# Sheet1.net
KiCad netlist of a schematic drawn in Altium Designer
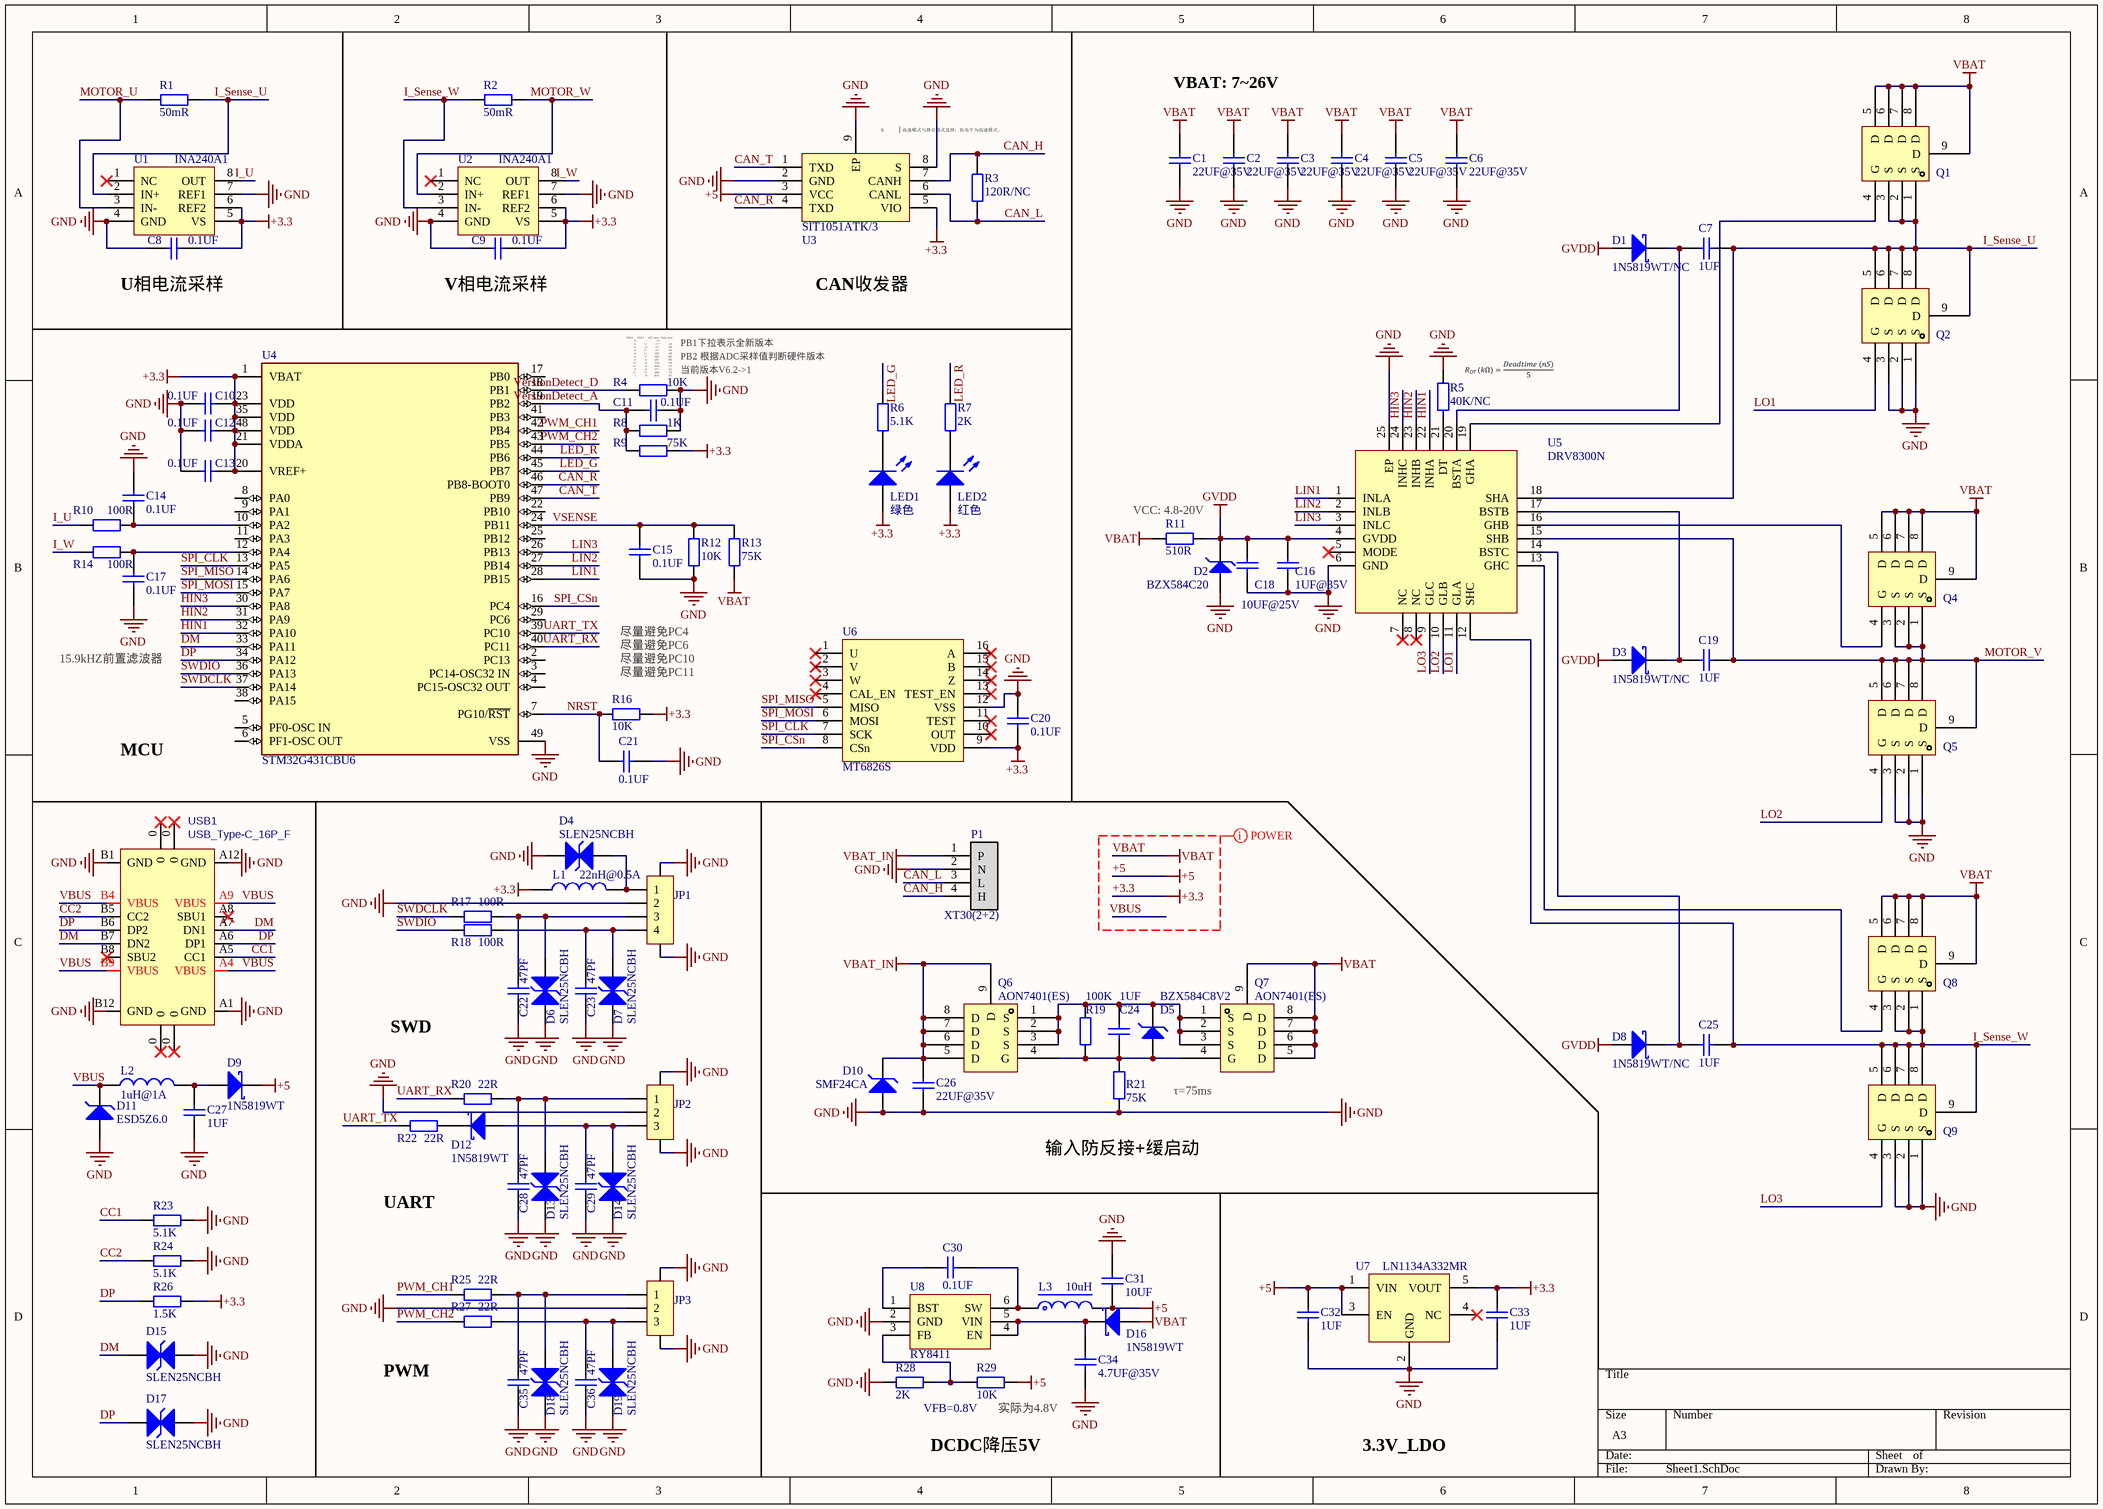
[diagram p0: Sheet1.SchDoc]

(export (version "E")
  (design (tool "Eeschema 10.0.6"))
  (components
    (comp (ref "C1")
      (value "22UF@35V")
      (footprint "C1206_NS")
      (description "贴片电容/MLCC电容")
      (libsource (lib "阻容") (part "C"))
    )
    (comp (ref "C2")
      (value "22UF@35V")
      (footprint "C1206_NS")
      (description "贴片电容/MLCC电容")
      (libsource (lib "阻容") (part "C"))
    )
    (comp (ref "C3")
      (value "22UF@35V")
      (footprint "C1206_NS")
      (description "贴片电容/MLCC电容")
      (libsource (lib "阻容") (part "C"))
    )
    (comp (ref "C4")
      (value "22UF@35V")
      (footprint "C1206_NS")
      (description "贴片电容/MLCC电容")
      (libsource (lib "阻容") (part "C"))
    )
    (comp (ref "C5")
      (value "22UF@35V")
      (footprint "C1206_NS")
      (description "贴片电容/MLCC电容")
      (libsource (lib "阻容") (part "C"))
    )
    (comp (ref "C6")
      (value "22UF@35V")
      (footprint "C1206_NS")
      (description "贴片电容/MLCC电容")
      (libsource (lib "阻容") (part "C"))
    )
    (comp (ref "C7")
      (value "1UF")
      (footprint "C0603_NS")
      (description "贴片电容/MLCC电容")
      (libsource (lib "阻容") (part "C"))
    )
    (comp (ref "C8")
      (value "0.1UF")
      (footprint "C0402_NS")
      (description "贴片电容/MLCC电容")
      (libsource (lib "阻容") (part "C"))
    )
    (comp (ref "C9")
      (value "0.1UF")
      (footprint "C0402_NS")
      (description "贴片电容/MLCC电容")
      (libsource (lib "阻容") (part "C"))
    )
    (comp (ref "C10")
      (value "0.1UF")
      (footprint "C0402_NS")
      (description "贴片电容/MLCC电容")
      (libsource (lib "阻容") (part "C"))
    )
    (comp (ref "C11")
      (value "0.1UF")
      (footprint "C0402_NS")
      (description "贴片电容/MLCC电容")
      (libsource (lib "阻容") (part "C"))
    )
    (comp (ref "C12")
      (value "0.1UF")
      (footprint "C0402_NS")
      (description "贴片电容/MLCC电容")
      (libsource (lib "阻容") (part "C"))
    )
    (comp (ref "C13")
      (value "0.1UF")
      (footprint "C0402_NS")
      (description "贴片电容/MLCC电容")
      (libsource (lib "阻容") (part "C"))
    )
    (comp (ref "C14")
      (value "0.1UF")
      (footprint "C0402_NS")
      (description "贴片电容/MLCC电容")
      (libsource (lib "阻容") (part "C"))
    )
    (comp (ref "C15")
      (value "0.1UF")
      (footprint "C0402_NS")
      (description "贴片电容/MLCC电容")
      (libsource (lib "阻容") (part "C"))
    )
    (comp (ref "C16")
      (value "1UF@35V")
      (footprint "C0603_NS")
      (description "贴片电容/MLCC电容")
      (libsource (lib "阻容") (part "C"))
    )
    (comp (ref "C17")
      (value "0.1UF")
      (footprint "C0402_NS")
      (description "贴片电容/MLCC电容")
      (libsource (lib "阻容") (part "C"))
    )
    (comp (ref "C18")
      (value "10UF@25V")
      (footprint "C0603_NS")
      (description "贴片电容/MLCC电容")
      (libsource (lib "阻容") (part "C"))
    )
    (comp (ref "C19")
      (value "1UF")
      (footprint "C0603_NS")
      (description "贴片电容/MLCC电容")
      (libsource (lib "阻容") (part "C"))
    )
    (comp (ref "C20")
      (value "0.1UF")
      (footprint "C0402_NS")
      (description "贴片电容/MLCC电容")
      (libsource (lib "阻容") (part "C"))
    )
    (comp (ref "C21")
      (value "0.1UF")
      (footprint "C0402_NS")
      (description "贴片电容/MLCC电容")
      (libsource (lib "阻容") (part "C"))
    )
    (comp (ref "C22")
      (value "47PF")
      (footprint "C0402_NS")
      (description "贴片电容/MLCC电容")
      (libsource (lib "阻容") (part "C"))
    )
    (comp (ref "C23")
      (value "47PF")
      (footprint "C0402_NS")
      (description "贴片电容/MLCC电容")
      (libsource (lib "阻容") (part "C"))
    )
    (comp (ref "C24")
      (value "1UF")
      (footprint "C0402_NS")
      (description "贴片电容/MLCC电容")
      (libsource (lib "阻容") (part "C"))
    )
    (comp (ref "C25")
      (value "1UF")
      (footprint "C0603_NS")
      (description "贴片电容/MLCC电容")
      (libsource (lib "阻容") (part "C"))
    )
    (comp (ref "C26")
      (value "22UF@35V")
      (footprint "C1206_NS")
      (description "贴片电容/MLCC电容")
      (libsource (lib "阻容") (part "C"))
    )
    (comp (ref "C27")
      (value "1UF")
      (footprint "C0603_NS")
      (description "贴片电容/MLCC电容")
      (libsource (lib "阻容") (part "C"))
    )
    (comp (ref "C28")
      (value "47PF")
      (footprint "C0402_NS")
      (description "贴片电容/MLCC电容")
      (libsource (lib "阻容") (part "C"))
    )
    (comp (ref "C29")
      (value "47PF")
      (footprint "C0402_NS")
      (description "贴片电容/MLCC电容")
      (libsource (lib "阻容") (part "C"))
    )
    (comp (ref "C30")
      (value "0.1UF")
      (footprint "C0402_NS")
      (description "贴片电容/MLCC电容")
      (libsource (lib "阻容") (part "C"))
    )
    (comp (ref "C31")
      (value "10UF")
      (footprint "C0805_NS")
      (description "贴片电容/MLCC电容")
      (libsource (lib "阻容") (part "C"))
    )
    (comp (ref "C32")
      (value "1UF")
      (footprint "C0402_NS")
      (description "贴片电容/MLCC电容")
      (libsource (lib "阻容") (part "C"))
    )
    (comp (ref "C33")
      (value "1UF")
      (footprint "C0402_NS")
      (description "贴片电容/MLCC电容")
      (libsource (lib "阻容") (part "C"))
    )
    (comp (ref "C34")
      (value "4.7UF@35V")
      (footprint "C0805_NS")
      (description "贴片电容/MLCC电容")
      (libsource (lib "阻容") (part "C"))
    )
    (comp (ref "C35")
      (value "47PF")
      (footprint "C0402_NS")
      (description "贴片电容/MLCC电容")
      (libsource (lib "阻容") (part "C"))
    )
    (comp (ref "C36")
      (value "47PF")
      (footprint "C0402_NS")
      (description "贴片电容/MLCC电容")
      (libsource (lib "阻容") (part "C"))
    )
    (comp (ref "D1")
      (value "1N5819WT/NC")
      (footprint "SOD-523")
      (description "肖特基二极管")
      (libsource (lib "二极管(含LED)") (part "SSXX"))
    )
    (comp (ref "D2")
      (value "BZX584C20")
      (footprint "SOD-523")
      (description "稳压二极管")
      (fields (field (name "VOLTAGE") "5.1V"))
      (libsource (lib "二极管(含LED)") (part "MM1ZXX"))
    )
    (comp (ref "D3")
      (value "1N5819WT/NC")
      (footprint "SOD-523")
      (description "肖特基二极管")
      (libsource (lib "二极管(含LED)") (part "SSXX"))
    )
    (comp (ref "D4")
      (value "SLEN25NCBH")
      (footprint "DFN1006-2L_L1.0_W0.6_P0.7")
      (description "双向静电和浪涌保护(TVS/ESD)")
      (libsource (lib "二极管(含LED)") (part "PESD5V0F1BL"))
    )
    (comp (ref "D5")
      (value "BZX584C8V2")
      (footprint "SOD-523")
      (description "稳压二极管")
      (fields (field (name "VOLTAGE") "5.1V"))
      (libsource (lib "二极管(含LED)") (part "MM1ZXX"))
    )
    (comp (ref "D6")
      (value "SLEN25NCBH")
      (footprint "DFN1006-2L_L1.0_W0.6_P0.7")
      (description "双向静电和浪涌保护(TVS/ESD)")
      (libsource (lib "二极管(含LED)") (part "PESD5V0F1BL"))
    )
    (comp (ref "D7")
      (value "SLEN25NCBH")
      (footprint "DFN1006-2L_L1.0_W0.6_P0.7")
      (description "双向静电和浪涌保护(TVS/ESD)")
      (libsource (lib "二极管(含LED)") (part "PESD5V0F1BL"))
    )
    (comp (ref "D8")
      (value "1N5819WT/NC")
      (footprint "SOD-523")
      (description "肖特基二极管")
      (libsource (lib "二极管(含LED)") (part "SSXX"))
    )
    (comp (ref "D9")
      (value "1N5819WT")
      (footprint "SOD-523")
      (description "肖特基二极管")
      (libsource (lib "二极管(含LED)") (part "SSXX"))
    )
    (comp (ref "D10")
      (value "SMF24CA")
      (footprint "SOD-123")
      (description "TVS通用")
      (libsource (lib "二极管(含LED)") (part "TVS"))
    )
    (comp (ref "D11")
      (value "ESD5Z6.0")
      (footprint "SOD-523")
      (description "TVS通用")
      (libsource (lib "二极管(含LED)") (part "TVS"))
    )
    (comp (ref "D12")
      (value "1N5819WT")
      (footprint "SOD-523")
      (description "肖特基二极管")
      (libsource (lib "二极管(含LED)") (part "SSXX"))
    )
    (comp (ref "D13")
      (value "SLEN25NCBH")
      (footprint "DFN1006-2L_L1.0_W0.6_P0.7")
      (description "双向静电和浪涌保护(TVS/ESD)")
      (libsource (lib "二极管(含LED)") (part "PESD5V0F1BL"))
    )
    (comp (ref "D14")
      (value "SLEN25NCBH")
      (footprint "DFN1006-2L_L1.0_W0.6_P0.7")
      (description "双向静电和浪涌保护(TVS/ESD)")
      (libsource (lib "二极管(含LED)") (part "PESD5V0F1BL"))
    )
    (comp (ref "D15")
      (value "SLEN25NCBH")
      (footprint "DFN1006-2L_L1.0_W0.6_P0.7")
      (description "双向静电和浪涌保护(TVS/ESD)")
      (libsource (lib "二极管(含LED)") (part "PESD5V0F1BL"))
    )
    (comp (ref "D16")
      (value "1N5819WT")
      (footprint "SOD-523")
      (description "肖特基二极管")
      (libsource (lib "二极管(含LED)") (part "SSXX"))
    )
    (comp (ref "D17")
      (value "SLEN25NCBH")
      (footprint "DFN1006-2L_L1.0_W0.6_P0.7")
      (description "双向静电和浪涌保护(TVS/ESD)")
      (libsource (lib "二极管(含LED)") (part "PESD5V0F1BL"))
    )
    (comp (ref "D18")
      (value "SLEN25NCBH")
      (footprint "DFN1006-2L_L1.0_W0.6_P0.7")
      (description "双向静电和浪涌保护(TVS/ESD)")
      (libsource (lib "二极管(含LED)") (part "PESD5V0F1BL"))
    )
    (comp (ref "D19")
      (value "SLEN25NCBH")
      (footprint "DFN1006-2L_L1.0_W0.6_P0.7")
      (description "双向静电和浪涌保护(TVS/ESD)")
      (libsource (lib "二极管(含LED)") (part "PESD5V0F1BL"))
    )
    (comp (ref "JP1")
      (value "CON-4P")
      (footprint "HC0.8-WT-4P")
      (description "4P连接器")
      (libsource (lib "0.80mm连接器") (part "Header 4"))
    )
    (comp (ref "JP2")
      (value "CON-3P")
      (footprint "SH1.0-WT-3P")
      (description "3P连接器")
      (libsource (lib "1.00mm连接器") (part "Header 3"))
    )
    (comp (ref "JP3")
      (value "CON-3P")
      (footprint "SH1.0-WT-3P")
      (description "3P连接器")
      (libsource (lib "1.00mm连接器") (part "Header 3"))
    )
    (comp (ref "L1")
      (value "22nH@0.5A")
      (footprint "L0402_NS")
      (description "小功率贴片电感")
      (libsource (lib "电感") (part "L"))
    )
    (comp (ref "L2")
      (value "1uH@1A")
      (footprint "L1206_NS")
      (description "小功率贴片电感")
      (libsource (lib "电感") (part "L"))
    )
    (comp (ref "L3")
      (value "10uH")
      (footprint "NR3015")
      (description "太诱-NR磁胶电感")
      (libsource (lib "电感") (part "L-NR"))
    )
    (comp (ref "LED1")
      (value "绿色")
      (footprint "LED0402_NS")
      (description "贴片LED")
      (libsource (lib "二极管(含LED)") (part "LED"))
    )
    (comp (ref "LED2")
      (value "红色")
      (footprint "LED0402_NS")
      (description "贴片LED")
      (libsource (lib "二极管(含LED)") (part "LED"))
    )
    (comp (ref "P1")
      (value "XT30(2+2)")
      (footprint "XT30(2+2)PW-M")
      (description "XT30(2+2)连接器")
      (libsource (lib "接口") (part "XT30(2+2)"))
    )
    (comp (ref "Q1")
      (value "AON7410")
      (footprint "DFN8_L3.3_W3.3_P0.65")
      (libsource (lib "三极管-MOS管") (part "WSD3066DN33"))
    )
    (comp (ref "Q2")
      (value "AON7410")
      (footprint "DFN8_L3.3_W3.3_P0.65")
      (libsource (lib "三极管-MOS管") (part "WSD3066DN33"))
    )
    (comp (ref "Q4")
      (value "AON7410")
      (footprint "DFN8_L3.3_W3.3_P0.65")
      (libsource (lib "三极管-MOS管") (part "WSD3066DN33"))
    )
    (comp (ref "Q5")
      (value "AON7410")
      (footprint "DFN8_L3.3_W3.3_P0.65")
      (libsource (lib "三极管-MOS管") (part "WSD3066DN33"))
    )
    (comp (ref "Q6")
      (value "AON7401(ES)")
      (footprint "DFN8_L3.3_W3.3_P0.65")
      (description "类型:P沟道;漏源电压(Vdss):30V;连续漏极电流(Id):30A;功率(Pd):30W;导通电阻(RDS(on)@Vgs,Id):13mΩ@10V,8A;")
      (libsource (lib "三极管-MOS管") (part "FH13P04G6"))
    )
    (comp (ref "Q7")
      (value "AON7401(ES)")
      (footprint "DFN8_L3.3_W3.3_P0.65")
      (description "类型:P沟道;漏源电压(Vdss):30V;连续漏极电流(Id):30A;功率(Pd):30W;导通电阻(RDS(on)@Vgs,Id):13mΩ@10V,8A;")
      (libsource (lib "") (part "FH13P04G6_1"))
    )
    (comp (ref "Q8")
      (value "AON7410")
      (footprint "DFN8_L3.3_W3.3_P0.65")
      (libsource (lib "三极管-MOS管") (part "WSD3066DN33"))
    )
    (comp (ref "Q9")
      (value "AON7410")
      (footprint "DFN8_L3.3_W3.3_P0.65")
      (libsource (lib "三极管-MOS管") (part "WSD3066DN33"))
    )
    (comp (ref "R1")
      (value "50mR")
      (footprint "R1206_NS")
      (description "贴片电阻")
      (libsource (lib "阻容") (part "R"))
    )
    (comp (ref "R2")
      (value "50mR")
      (footprint "R1206_NS")
      (description "贴片电阻")
      (libsource (lib "阻容") (part "R"))
    )
    (comp (ref "R3")
      (value "120R/NC")
      (footprint "R0603_NS")
      (description "贴片电阻")
      (libsource (lib "阻容") (part "R"))
    )
    (comp (ref "R4")
      (value "10K")
      (footprint "R0402_NS")
      (description "贴片电阻")
      (libsource (lib "阻容") (part "R"))
    )
    (comp (ref "R5")
      (value "40K/NC")
      (footprint "R0402_NS")
      (description "贴片电阻")
      (libsource (lib "阻容") (part "R"))
    )
    (comp (ref "R6")
      (value "5.1K")
      (footprint "R0402_NS")
      (description "贴片电阻")
      (libsource (lib "阻容") (part "R"))
    )
    (comp (ref "R7")
      (value "2K")
      (footprint "R0402_NS")
      (description "贴片电阻")
      (libsource (lib "阻容") (part "R"))
    )
    (comp (ref "R8")
      (value "1K")
      (footprint "R0402_NS")
      (description "贴片电阻")
      (libsource (lib "阻容") (part "R"))
    )
    (comp (ref "R9")
      (value "75K")
      (footprint "R0402_NS")
      (description "贴片电阻")
      (libsource (lib "阻容") (part "R"))
    )
    (comp (ref "R10")
      (value "100R")
      (footprint "R0402_NS")
      (description "贴片电阻")
      (libsource (lib "阻容") (part "R"))
    )
    (comp (ref "R11")
      (value "510R")
      (footprint "R0603_NS")
      (description "贴片电阻")
      (libsource (lib "阻容") (part "R"))
    )
    (comp (ref "R12")
      (value "10K")
      (footprint "R0402_NS")
      (description "贴片电阻")
      (libsource (lib "阻容") (part "R"))
    )
    (comp (ref "R13")
      (value "75K")
      (footprint "R0402_NS")
      (description "贴片电阻")
      (libsource (lib "阻容") (part "R"))
    )
    (comp (ref "R14")
      (value "100R")
      (footprint "R0402_NS")
      (description "贴片电阻")
      (libsource (lib "阻容") (part "R"))
    )
    (comp (ref "R16")
      (value "10K")
      (footprint "R0402_NS")
      (description "贴片电阻")
      (libsource (lib "阻容") (part "R"))
    )
    (comp (ref "R17")
      (value "100R")
      (footprint "R0402_NS")
      (description "贴片电阻")
      (libsource (lib "阻容") (part "R"))
    )
    (comp (ref "R18")
      (value "100R")
      (footprint "R0402_NS")
      (description "贴片电阻")
      (libsource (lib "阻容") (part "R"))
    )
    (comp (ref "R19")
      (value "100K")
      (footprint "R0402_NS")
      (description "贴片电阻")
      (libsource (lib "阻容") (part "R"))
    )
    (comp (ref "R20")
      (value "22R")
      (footprint "R0402_NS")
      (description "贴片电阻")
      (libsource (lib "阻容") (part "R"))
    )
    (comp (ref "R21")
      (value "75K")
      (footprint "R0402_NS")
      (description "贴片电阻")
      (libsource (lib "阻容") (part "R"))
    )
    (comp (ref "R22")
      (value "22R")
      (footprint "R0402_NS")
      (description "贴片电阻")
      (libsource (lib "阻容") (part "R"))
    )
    (comp (ref "R23")
      (value "5.1K")
      (footprint "R0402_NS")
      (description "贴片电阻")
      (libsource (lib "阻容") (part "R"))
    )
    (comp (ref "R24")
      (value "5.1K")
      (footprint "R0402_NS")
      (description "贴片电阻")
      (libsource (lib "阻容") (part "R"))
    )
    (comp (ref "R25")
      (value "22R")
      (footprint "R0402_NS")
      (description "贴片电阻")
      (libsource (lib "阻容") (part "R"))
    )
    (comp (ref "R26")
      (value "1.5K")
      (footprint "R0402_NS")
      (description "贴片电阻")
      (libsource (lib "阻容") (part "R"))
    )
    (comp (ref "R27")
      (value "22R")
      (footprint "R0402_NS")
      (description "贴片电阻")
      (libsource (lib "阻容") (part "R"))
    )
    (comp (ref "R28")
      (value "2K")
      (footprint "R0402_NS")
      (description "贴片电阻")
      (libsource (lib "阻容") (part "R"))
    )
    (comp (ref "R29")
      (value "10K")
      (footprint "R0402_NS")
      (description "贴片电阻")
      (libsource (lib "阻容") (part "R"))
    )
    (comp (ref "U1")
      (value "INA240A1")
      (footprint "TSSOP8_L4.4_W3.0_P0.65")
      (description "具有增强的 PWM 抑制能力的 -4V 至 80V、双向、超精密电流感应放大器")
      (libsource (lib "运放") (part "INA240"))
    )
    (comp (ref "U2")
      (value "INA240A1")
      (footprint "TSSOP8_L4.4_W3.0_P0.65")
      (description "具有增强的 PWM 抑制能力的 -4V 至 80V、双向、超精密电流感应放大器")
      (libsource (lib "运放") (part "INA240"))
    )
    (comp (ref "U3")
      (value "SIT1051ATK/3")
      (footprint "DFN8_L3.0_W3.0_P0.65")
      (description "5V 供电， IO 口兼容 3.3V，± 70V 总线耐压， CAN FD 静音模式总线收发器")
      (libsource (lib "协议芯片") (part "SIT1051ATK/3"))
    )
    (comp (ref "U4")
      (value "STM32G431CBU6")
      (footprint "QFN48_L7.0_W7.0_P0.5")
      (description "Microcontroller 32-Bit ARM Cortex-M4 RISC 128KB Flash 1.71V to 3.6V QFN48")
      (fields
        (field (name "MANUFACTURER") "STMicroelectronics")
        (field (name "OCTOPART") "https://octopart.com/stm32g431cbt6-stmicroelectronics-98835224")
      )
      (libsource (lib "2.1 - STM32 G0及G4系列单片机") (part "STM32G431CBU6"))
    )
    (comp (ref "U5")
      (value "DRV8300N")
      (footprint "QFN24_L4.0_W4.0_P0.5")
      (description "具有自举二极管的最大 100V 简单三相栅极驱动器")
      (libsource (lib "电机驱动IC") (part "DRV8300D"))
    )
    (comp (ref "U6")
      (value "MT6826S")
      (footprint "TSSOP16_L5.0_W4.4_P0.65")
      (description "15位高分辨率、高速磁性角度编码器IC")
      (libsource (lib "其他") (part "MT6826S"))
    )
    (comp (ref "U7")
      (value "LN1134A332MR")
      (footprint "SOT23-5_L3.0_W1.7_P0.95")
      (libsource (lib "LDO") (part "RT9013-33GB"))
    )
    (comp (ref "U8")
      (value "RY8411")
      (footprint "SOT23-6_L3.0_W1.7_P0.95")
      (description "40V/1A/1.1MHz同步降压转换器")
      (libsource (lib "电源IC") (part "JW5026"))
    )
    (comp (ref "USB1")
      (value "USB_Type-C_16P_F")
      (footprint "USB_Type-C_SMD_16P_F")
      (description "USB_Type-C母座")
      (libsource (lib "接口") (part "USB_Type-C_16P_F"))
    )
  )
  (nets
    (net (code "1") (name "+3.3") (class "Default")
      (node (ref "C10") (pin "1") (pinfunction "1_1") (pintype "passive"))
      (node (ref "C12") (pin "1") (pinfunction "1_1") (pintype "passive"))
      (node (ref "C13") (pin "1") (pinfunction "1_1") (pintype "passive"))
      (node (ref "C20") (pin "2") (pinfunction "2_2") (pintype "passive"))
      (node (ref "C33") (pin "2") (pinfunction "2_2") (pintype "passive"))
      (node (ref "C8") (pin "2") (pinfunction "2_2") (pintype "passive"))
      (node (ref "C9") (pin "2") (pinfunction "2_2") (pintype "passive"))
      (node (ref "L1") (pin "1") (pinfunction "1_1") (pintype "passive"))
      (node (ref "LED1") (pin "1") (pinfunction "A_1") (pintype "passive"))
      (node (ref "LED2") (pin "1") (pinfunction "A_1") (pintype "passive"))
      (node (ref "R16") (pin "2") (pinfunction "2_2") (pintype "passive"))
      (node (ref "R26") (pin "2") (pinfunction "2_2") (pintype "passive"))
      (node (ref "R9") (pin "2") (pinfunction "2_2") (pintype "passive"))
      (node (ref "U1") (pin "5") (pinfunction "VS_5") (pintype "passive"))
      (node (ref "U1") (pin "6") (pinfunction "REF2_6") (pintype "passive"))
      (node (ref "U2") (pin "5") (pinfunction "VS_5") (pintype "passive"))
      (node (ref "U2") (pin "6") (pinfunction "REF2_6") (pintype "passive"))
      (node (ref "U3") (pin "5") (pinfunction "VIO_5") (pintype "passive"))
      (node (ref "U4") (pin "1") (pinfunction "VBAT_1") (pintype "power_in"))
      (node (ref "U4") (pin "20") (pinfunction "VREF+_20") (pintype "power_in"))
      (node (ref "U4") (pin "21") (pinfunction "VDDA_21") (pintype "power_in"))
      (node (ref "U4") (pin "23") (pinfunction "VDD_23") (pintype "power_in"))
      (node (ref "U4") (pin "35") (pinfunction "VDD_35") (pintype "power_in"))
      (node (ref "U4") (pin "48") (pinfunction "VDD_48") (pintype "power_in"))
      (node (ref "U6") (pin "9") (pinfunction "VDD_9") (pintype "passive"))
      (node (ref "U7") (pin "5") (pinfunction "VOUT_5") (pintype "passive"))
    )
    (net (code "2") (name "+5") (class "Default")
      (node (ref "C31") (pin "2") (pinfunction "2_2") (pintype "passive"))
      (node (ref "C32") (pin "2") (pinfunction "2_2") (pintype "passive"))
      (node (ref "D9") (pin "2") (pinfunction "K_2") (pintype "passive"))
      (node (ref "L3") (pin "2") (pinfunction "2_2") (pintype "passive"))
      (node (ref "R29") (pin "1") (pinfunction "1_1") (pintype "passive"))
      (node (ref "U3") (pin "3") (pinfunction "VCC_3") (pintype "passive"))
      (node (ref "U7") (pin "1") (pinfunction "VIN_1") (pintype "passive"))
      (node (ref "U7") (pin "3") (pinfunction "EN_3") (pintype "passive"))
    )
    (net (code "3") (name "/CAN_H") (class "Default")
      (node (ref "P1") (pin "4") (pinfunction "H_4") (pintype "passive"))
      (node (ref "R3") (pin "2") (pinfunction "2_2") (pintype "passive"))
      (node (ref "U3") (pin "7") (pinfunction "CANH_7") (pintype "passive"))
    )
    (net (code "4") (name "/CAN_L") (class "Default")
      (node (ref "P1") (pin "3") (pinfunction "L_3") (pintype "passive"))
      (node (ref "R3") (pin "1") (pinfunction "1_1") (pintype "passive"))
      (node (ref "U3") (pin "6") (pinfunction "CANL_6") (pintype "passive"))
    )
    (net (code "5") (name "/CAN_R") (class "Default")
      (node (ref "U3") (pin "4") (pinfunction "TXD_4") (pintype "passive"))
      (node (ref "U4") (pin "46") (pinfunction "PB8-BOOT0_46") (pintype "bidirectional"))
    )
    (net (code "6") (name "/CAN_T") (class "Default")
      (node (ref "U3") (pin "1") (pinfunction "TXD_1") (pintype "passive"))
      (node (ref "U4") (pin "47") (pinfunction "PB9_47") (pintype "bidirectional"))
    )
    (net (code "7") (name "/CC1") (class "Default")
      (node (ref "R23") (pin "2") (pinfunction "2_2") (pintype "passive"))
      (node (ref "USB1") (pin "A5") (pinfunction "CC1_A5") (pintype "passive"))
    )
    (net (code "8") (name "/CC2") (class "Default")
      (node (ref "R24") (pin "2") (pinfunction "2_2") (pintype "passive"))
      (node (ref "USB1") (pin "B5") (pinfunction "CC2_B5") (pintype "passive"))
    )
    (net (code "9") (name "/DM") (class "Default")
      (node (ref "D15") (pin "1") (pinfunction "A_1") (pintype "passive"))
      (node (ref "U4") (pin "33") (pinfunction "PA11_33") (pintype "bidirectional"))
      (node (ref "USB1") (pin "A7") (pinfunction "DN1_A7") (pintype "passive"))
      (node (ref "USB1") (pin "B7") (pinfunction "DN2_B7") (pintype "passive"))
    )
    (net (code "10") (name "/DP") (class "Default")
      (node (ref "D17") (pin "1") (pinfunction "A_1") (pintype "passive"))
      (node (ref "R26") (pin "1") (pinfunction "1_1") (pintype "passive"))
      (node (ref "U4") (pin "34") (pinfunction "PA12_34") (pintype "bidirectional"))
      (node (ref "USB1") (pin "A6") (pinfunction "DP1_A6") (pintype "passive"))
      (node (ref "USB1") (pin "B6") (pinfunction "DP2_B6") (pintype "passive"))
    )
    (net (code "11") (name "/HIN1") (class "Default")
      (node (ref "U4") (pin "32") (pinfunction "PA10_32") (pintype "bidirectional"))
      (node (ref "U5") (pin "22") (pinfunction "INHA_22") (pintype "passive"))
    )
    (net (code "12") (name "/HIN2") (class "Default")
      (node (ref "U4") (pin "31") (pinfunction "PA9_31") (pintype "bidirectional"))
      (node (ref "U5") (pin "23") (pinfunction "INHB_23") (pintype "passive"))
    )
    (net (code "13") (name "/HIN3") (class "Default")
      (node (ref "U4") (pin "30") (pinfunction "PA8_30") (pintype "bidirectional"))
      (node (ref "U5") (pin "24") (pinfunction "INHC_24") (pintype "passive"))
    )
    (net (code "14") (name "/I_Sense_U") (class "Default")
      (node (ref "C7") (pin "1") (pinfunction "1_1") (pintype "passive"))
      (node (ref "Q1") (pin "1") (pinfunction "S_1") (pintype "passive"))
      (node (ref "Q1") (pin "2") (pinfunction "S_2") (pintype "passive"))
      (node (ref "Q1") (pin "3") (pinfunction "S_3") (pintype "passive"))
      (node (ref "Q2") (pin "5") (pinfunction "D_5") (pintype "passive"))
      (node (ref "Q2") (pin "6") (pinfunction "D_6") (pintype "passive"))
      (node (ref "Q2") (pin "7") (pinfunction "D_7") (pintype "passive"))
      (node (ref "Q2") (pin "8") (pinfunction "D_8") (pintype "passive"))
      (node (ref "Q2") (pin "9") (pinfunction "D_9") (pintype "passive"))
      (node (ref "R1") (pin "1") (pinfunction "1_1") (pintype "passive"))
      (node (ref "U1") (pin "2") (pinfunction "IN+_2") (pintype "passive"))
      (node (ref "U5") (pin "18") (pinfunction "SHA_18") (pintype "passive"))
    )
    (net (code "15") (name "/I_Sense_W") (class "Default")
      (node (ref "C25") (pin "1") (pinfunction "1_1") (pintype "passive"))
      (node (ref "Q8") (pin "1") (pinfunction "S_1") (pintype "passive"))
      (node (ref "Q8") (pin "2") (pinfunction "S_2") (pintype "passive"))
      (node (ref "Q8") (pin "3") (pinfunction "S_3") (pintype "passive"))
      (node (ref "Q9") (pin "5") (pinfunction "D_5") (pintype "passive"))
      (node (ref "Q9") (pin "6") (pinfunction "D_6") (pintype "passive"))
      (node (ref "Q9") (pin "7") (pinfunction "D_7") (pintype "passive"))
      (node (ref "Q9") (pin "8") (pinfunction "D_8") (pintype "passive"))
      (node (ref "Q9") (pin "9") (pinfunction "D_9") (pintype "passive"))
      (node (ref "R2") (pin "2") (pinfunction "2_2") (pintype "passive"))
      (node (ref "U2") (pin "3") (pinfunction "IN-_3") (pintype "passive"))
      (node (ref "U5") (pin "12") (pinfunction "SHC_12") (pintype "passive"))
    )
    (net (code "16") (name "/I_U") (class "Default")
      (node (ref "R10") (pin "2") (pinfunction "2_2") (pintype "passive"))
      (node (ref "U1") (pin "8") (pinfunction "OUT_8") (pintype "passive"))
    )
    (net (code "17") (name "/I_W") (class "Default")
      (node (ref "R14") (pin "2") (pinfunction "2_2") (pintype "passive"))
      (node (ref "U2") (pin "8") (pinfunction "OUT_8") (pintype "passive"))
    )
    (net (code "18") (name "/LED_G") (class "Default")
      (node (ref "R6") (pin "1") (pinfunction "1_1") (pintype "passive"))
      (node (ref "U4") (pin "45") (pinfunction "PB7_45") (pintype "bidirectional"))
    )
    (net (code "19") (name "/LED_R") (class "Default")
      (node (ref "R7") (pin "1") (pinfunction "1_1") (pintype "passive"))
      (node (ref "U4") (pin "44") (pinfunction "PB6_44") (pintype "bidirectional"))
    )
    (net (code "20") (name "/LIN1") (class "Default")
      (node (ref "U4") (pin "28") (pinfunction "PB15_28") (pintype "bidirectional"))
      (node (ref "U5") (pin "1") (pinfunction "INLA_1") (pintype "passive"))
    )
    (net (code "21") (name "/LIN2") (class "Default")
      (node (ref "U4") (pin "27") (pinfunction "PB14_27") (pintype "bidirectional"))
      (node (ref "U5") (pin "2") (pinfunction "INLB_2") (pintype "passive"))
    )
    (net (code "22") (name "/LIN3") (class "Default")
      (node (ref "U4") (pin "26") (pinfunction "PB13_26") (pintype "bidirectional"))
      (node (ref "U5") (pin "3") (pinfunction "INLC_3") (pintype "passive"))
    )
    (net (code "23") (name "/LO1") (class "Default")
      (node (ref "Q2") (pin "4") (pinfunction "G_4") (pintype "passive"))
      (node (ref "U5") (pin "11") (pinfunction "GLA_11") (pintype "passive"))
    )
    (net (code "24") (name "/LO2") (class "Default")
      (node (ref "Q5") (pin "4") (pinfunction "G_4") (pintype "passive"))
      (node (ref "U5") (pin "10") (pinfunction "GLB_10") (pintype "passive"))
    )
    (net (code "25") (name "/LO3") (class "Default")
      (node (ref "Q9") (pin "4") (pinfunction "G_4") (pintype "passive"))
      (node (ref "U5") (pin "9") (pinfunction "GLC_9") (pintype "passive"))
    )
    (net (code "26") (name "/MOTOR_U") (class "Default")
      (node (ref "R1") (pin "2") (pinfunction "2_2") (pintype "passive"))
      (node (ref "U1") (pin "3") (pinfunction "IN-_3") (pintype "passive"))
    )
    (net (code "27") (name "/MOTOR_V") (class "Default")
      (node (ref "C19") (pin "1") (pinfunction "1_1") (pintype "passive"))
      (node (ref "Q4") (pin "1") (pinfunction "S_1") (pintype "passive"))
      (node (ref "Q4") (pin "2") (pinfunction "S_2") (pintype "passive"))
      (node (ref "Q4") (pin "3") (pinfunction "S_3") (pintype "passive"))
      (node (ref "Q5") (pin "5") (pinfunction "D_5") (pintype "passive"))
      (node (ref "Q5") (pin "6") (pinfunction "D_6") (pintype "passive"))
      (node (ref "Q5") (pin "7") (pinfunction "D_7") (pintype "passive"))
      (node (ref "Q5") (pin "8") (pinfunction "D_8") (pintype "passive"))
      (node (ref "Q5") (pin "9") (pinfunction "D_9") (pintype "passive"))
      (node (ref "U5") (pin "15") (pinfunction "SHB_15") (pintype "passive"))
    )
    (net (code "28") (name "/MOTOR_W") (class "Default")
      (node (ref "R2") (pin "1") (pinfunction "1_1") (pintype "passive"))
      (node (ref "U2") (pin "2") (pinfunction "IN+_2") (pintype "passive"))
    )
    (net (code "29") (name "/NRST") (class "Default")
      (node (ref "C21") (pin "2") (pinfunction "2_2") (pintype "passive"))
      (node (ref "R16") (pin "1") (pinfunction "1_1") (pintype "passive"))
      (node (ref "U4") (pin "7") (pinfunction "PG10/~{RST}_7") (pintype "bidirectional"))
    )
    (net (code "30") (name "/PWM_CH1") (class "Default")
      (node (ref "R25") (pin "1") (pinfunction "1_1") (pintype "passive"))
      (node (ref "U4") (pin "42") (pinfunction "PB4_42") (pintype "bidirectional"))
    )
    (net (code "31") (name "/PWM_CH2") (class "Default")
      (node (ref "R27") (pin "1") (pinfunction "1_1") (pintype "passive"))
      (node (ref "U4") (pin "43") (pinfunction "PB5_43") (pintype "bidirectional"))
    )
    (net (code "32") (name "/SPI_CLK") (class "Default")
      (node (ref "U4") (pin "13") (pinfunction "PA5_13") (pintype "bidirectional"))
      (node (ref "U6") (pin "7") (pinfunction "SCK_7") (pintype "passive"))
    )
    (net (code "33") (name "/SPI_CSn") (class "Default")
      (node (ref "U4") (pin "16") (pinfunction "PC4_16") (pintype "bidirectional"))
      (node (ref "U6") (pin "8") (pinfunction "CSn_8") (pintype "passive"))
    )
    (net (code "34") (name "/SPI_MISO") (class "Default")
      (node (ref "U4") (pin "14") (pinfunction "PA6_14") (pintype "bidirectional"))
      (node (ref "U6") (pin "5") (pinfunction "MISO_5") (pintype "passive"))
    )
    (net (code "35") (name "/SPI_MOSI") (class "Default")
      (node (ref "U4") (pin "15") (pinfunction "PA7_15") (pintype "bidirectional"))
      (node (ref "U6") (pin "6") (pinfunction "MOSI_6") (pintype "passive"))
    )
    (net (code "36") (name "/SWDCLK") (class "Default")
      (node (ref "R17") (pin "1") (pinfunction "1_1") (pintype "passive"))
      (node (ref "U4") (pin "37") (pinfunction "PA14_37") (pintype "bidirectional"))
    )
    (net (code "37") (name "/SWDIO") (class "Default")
      (node (ref "R18") (pin "1") (pinfunction "1_1") (pintype "passive"))
      (node (ref "U4") (pin "36") (pinfunction "PA13_36") (pintype "bidirectional"))
    )
    (net (code "38") (name "/UART_RX") (class "Default")
      (node (ref "R20") (pin "1") (pinfunction "1_1") (pintype "passive"))
      (node (ref "U4") (pin "40") (pinfunction "PC11_40") (pintype "bidirectional"))
    )
    (net (code "39") (name "/UART_TX") (class "Default")
      (node (ref "R22") (pin "1") (pinfunction "1_1") (pintype "passive"))
      (node (ref "U4") (pin "39") (pinfunction "PC10_39") (pintype "bidirectional"))
    )
    (net (code "40") (name "/VBUS") (class "Default")
      (node (ref "D11") (pin "2") (pinfunction "K_2") (pintype "passive"))
      (node (ref "L2") (pin "1") (pinfunction "1_1") (pintype "passive"))
      (node (ref "USB1") (pin "A4") (pinfunction "VBUS_A4") (pintype "passive"))
      (node (ref "USB1") (pin "A9") (pinfunction "VBUS_A9") (pintype "passive"))
      (node (ref "USB1") (pin "B4") (pinfunction "VBUS_B4") (pintype "passive"))
      (node (ref "USB1") (pin "B9") (pinfunction "VBUS_B9") (pintype "passive"))
    )
    (net (code "41") (name "/VSENSE") (class "Default")
      (node (ref "C15") (pin "1") (pinfunction "1_1") (pintype "passive"))
      (node (ref "R12") (pin "2") (pinfunction "2_2") (pintype "passive"))
      (node (ref "R13") (pin "1") (pinfunction "1_1") (pintype "passive"))
      (node (ref "U4") (pin "24") (pinfunction "PB11_24") (pintype "bidirectional"))
    )
    (net (code "42") (name "/VersionDetect_A") (class "Default")
      (node (ref "C11") (pin "1") (pinfunction "1_1") (pintype "passive"))
      (node (ref "R8") (pin "1") (pinfunction "1_1") (pintype "passive"))
      (node (ref "R9") (pin "1") (pinfunction "1_1") (pintype "passive"))
      (node (ref "U4") (pin "19") (pinfunction "PB2_19") (pintype "bidirectional"))
    )
    (net (code "43") (name "/VersionDetect_D") (class "Default")
      (node (ref "R4") (pin "1") (pinfunction "1_1") (pintype "passive"))
      (node (ref "U4") (pin "18") (pinfunction "PB1_18") (pintype "bidirectional"))
    )
    (net (code "44") (name "GND") (class "Default")
      (node (ref "C1") (pin "2") (pinfunction "2_2") (pintype "passive"))
      (node (ref "C10") (pin "2") (pinfunction "2_2") (pintype "passive"))
      (node (ref "C11") (pin "2") (pinfunction "2_2") (pintype "passive"))
      (node (ref "C12") (pin "2") (pinfunction "2_2") (pintype "passive"))
      (node (ref "C13") (pin "2") (pinfunction "2_2") (pintype "passive"))
      (node (ref "C14") (pin "1") (pinfunction "1_1") (pintype "passive"))
      (node (ref "C15") (pin "2") (pinfunction "2_2") (pintype "passive"))
      (node (ref "C16") (pin "2") (pinfunction "2_2") (pintype "passive"))
      (node (ref "C17") (pin "2") (pinfunction "2_2") (pintype "passive"))
      (node (ref "C18") (pin "1") (pinfunction "1_1") (pintype "passive"))
      (node (ref "C2") (pin "2") (pinfunction "2_2") (pintype "passive"))
      (node (ref "C20") (pin "1") (pinfunction "1_1") (pintype "passive"))
      (node (ref "C21") (pin "1") (pinfunction "1_1") (pintype "passive"))
      (node (ref "C22") (pin "2") (pinfunction "2_2") (pintype "passive"))
      (node (ref "C23") (pin "2") (pinfunction "2_2") (pintype "passive"))
      (node (ref "C26") (pin "2") (pinfunction "2_2") (pintype "passive"))
      (node (ref "C27") (pin "1") (pinfunction "1_1") (pintype "passive"))
      (node (ref "C28") (pin "2") (pinfunction "2_2") (pintype "passive"))
      (node (ref "C29") (pin "2") (pinfunction "2_2") (pintype "passive"))
      (node (ref "C3") (pin "2") (pinfunction "2_2") (pintype "passive"))
      (node (ref "C31") (pin "1") (pinfunction "1_1") (pintype "passive"))
      (node (ref "C32") (pin "1") (pinfunction "1_1") (pintype "passive"))
      (node (ref "C33") (pin "1") (pinfunction "1_1") (pintype "passive"))
      (node (ref "C34") (pin "1") (pinfunction "1_1") (pintype "passive"))
      (node (ref "C35") (pin "2") (pinfunction "2_2") (pintype "passive"))
      (node (ref "C36") (pin "2") (pinfunction "2_2") (pintype "passive"))
      (node (ref "C4") (pin "2") (pinfunction "2_2") (pintype "passive"))
      (node (ref "C5") (pin "2") (pinfunction "2_2") (pintype "passive"))
      (node (ref "C6") (pin "2") (pinfunction "2_2") (pintype "passive"))
      (node (ref "C8") (pin "1") (pinfunction "1_1") (pintype "passive"))
      (node (ref "C9") (pin "1") (pinfunction "1_1") (pintype "passive"))
      (node (ref "D10") (pin "1") (pinfunction "A_1") (pintype "passive"))
      (node (ref "D11") (pin "1") (pinfunction "A_1") (pintype "passive"))
      (node (ref "D13") (pin "2") (pinfunction "K_2") (pintype "passive"))
      (node (ref "D14") (pin "2") (pinfunction "K_2") (pintype "passive"))
      (node (ref "D15") (pin "2") (pinfunction "K_2") (pintype "passive"))
      (node (ref "D17") (pin "2") (pinfunction "K_2") (pintype "passive"))
      (node (ref "D18") (pin "2") (pinfunction "K_2") (pintype "passive"))
      (node (ref "D19") (pin "2") (pinfunction "K_2") (pintype "passive"))
      (node (ref "D2") (pin "1") (pinfunction "A_1") (pintype "passive"))
      (node (ref "D4") (pin "2") (pinfunction "K_2") (pintype "passive"))
      (node (ref "D6") (pin "2") (pinfunction "K_2") (pintype "passive"))
      (node (ref "D7") (pin "2") (pinfunction "K_2") (pintype "passive"))
      (node (ref "JP1") (pin "0") (pinfunction "0_0") (pintype "passive"))
      (node (ref "JP1") (pin "2") (pinfunction "2_2") (pintype "passive"))
      (node (ref "JP2") (pin "0") (pinfunction "0_0") (pintype "passive"))
      (node (ref "JP2") (pin "2") (pinfunction "2_2") (pintype "passive"))
      (node (ref "JP3") (pin "0") (pinfunction "0_0") (pintype "passive"))
      (node (ref "JP3") (pin "2") (pinfunction "2_2") (pintype "passive"))
      (node (ref "P1") (pin "2") (pinfunction "N_2") (pintype "passive"))
      (node (ref "Q2") (pin "1") (pinfunction "S_1") (pintype "passive"))
      (node (ref "Q2") (pin "2") (pinfunction "S_2") (pintype "passive"))
      (node (ref "Q2") (pin "3") (pinfunction "S_3") (pintype "passive"))
      (node (ref "Q5") (pin "1") (pinfunction "S_1") (pintype "passive"))
      (node (ref "Q5") (pin "2") (pinfunction "S_2") (pintype "passive"))
      (node (ref "Q5") (pin "3") (pinfunction "S_3") (pintype "passive"))
      (node (ref "Q9") (pin "1") (pinfunction "S_1") (pintype "passive"))
      (node (ref "Q9") (pin "2") (pinfunction "S_2") (pintype "passive"))
      (node (ref "Q9") (pin "3") (pinfunction "S_3") (pintype "passive"))
      (node (ref "R12") (pin "1") (pinfunction "1_1") (pintype "passive"))
      (node (ref "R21") (pin "1") (pinfunction "1_1") (pintype "passive"))
      (node (ref "R23") (pin "1") (pinfunction "1_1") (pintype "passive"))
      (node (ref "R24") (pin "1") (pinfunction "1_1") (pintype "passive"))
      (node (ref "R28") (pin "2") (pinfunction "2_2") (pintype "passive"))
      (node (ref "R4") (pin "2") (pinfunction "2_2") (pintype "passive"))
      (node (ref "R5") (pin "2") (pinfunction "2_2") (pintype "passive"))
      (node (ref "R8") (pin "2") (pinfunction "2_2") (pintype "passive"))
      (node (ref "U1") (pin "4") (pinfunction "GND_4") (pintype "passive"))
      (node (ref "U1") (pin "7") (pinfunction "REF1_7") (pintype "passive"))
      (node (ref "U2") (pin "4") (pinfunction "GND_4") (pintype "passive"))
      (node (ref "U2") (pin "7") (pinfunction "REF1_7") (pintype "passive"))
      (node (ref "U3") (pin "2") (pinfunction "GND_2") (pintype "passive"))
      (node (ref "U3") (pin "8") (pinfunction "S_8") (pintype "passive"))
      (node (ref "U3") (pin "9") (pinfunction "EP_9") (pintype "passive"))
      (node (ref "U4") (pin "49") (pinfunction "VSS_49") (pintype "power_in"))
      (node (ref "U5") (pin "25") (pinfunction "EP_25") (pintype "passive"))
      (node (ref "U5") (pin "6") (pinfunction "GND_6") (pintype "passive"))
      (node (ref "U6") (pin "12") (pinfunction "VSS_12") (pintype "passive"))
      (node (ref "U7") (pin "2") (pinfunction "GND_2") (pintype "passive"))
      (node (ref "U8") (pin "2") (pinfunction "GND_2") (pintype "passive"))
      (node (ref "USB1") (pin "A1") (pinfunction "GND_A1") (pintype "passive"))
      (node (ref "USB1") (pin "A12") (pinfunction "GND_A12") (pintype "passive"))
      (node (ref "USB1") (pin "B1") (pinfunction "GND_B1") (pintype "passive"))
      (node (ref "USB1") (pin "B12") (pinfunction "GND_B12") (pintype "passive"))
    )
    (net (code "45") (name "GVDD") (class "Default")
      (node (ref "C16") (pin "1") (pinfunction "1_1") (pintype "passive"))
      (node (ref "C18") (pin "2") (pinfunction "2_2") (pintype "passive"))
      (node (ref "D1") (pin "1") (pinfunction "A_1") (pintype "passive"))
      (node (ref "D2") (pin "2") (pinfunction "K_2") (pintype "passive"))
      (node (ref "D3") (pin "1") (pinfunction "A_1") (pintype "passive"))
      (node (ref "D8") (pin "1") (pinfunction "A_1") (pintype "passive"))
      (node (ref "R11") (pin "2") (pinfunction "2_2") (pintype "passive"))
      (node (ref "U5") (pin "4") (pinfunction "GVDD_4") (pintype "passive"))
    )
    (net (code "46") (name "Net-(D1-K)") (class "Default")
      (node (ref "C7") (pin "2") (pinfunction "2_2") (pintype "passive"))
      (node (ref "D1") (pin "2") (pinfunction "K_2") (pintype "passive"))
      (node (ref "U5") (pin "20") (pinfunction "BSTA_20") (pintype "passive"))
    )
    (net (code "47") (name "Net-(D3-K)") (class "Default")
      (node (ref "C19") (pin "2") (pinfunction "2_2") (pintype "passive"))
      (node (ref "D3") (pin "2") (pinfunction "K_2") (pintype "passive"))
      (node (ref "U5") (pin "17") (pinfunction "BSTB_17") (pintype "passive"))
    )
    (net (code "48") (name "Net-(D4-A)") (class "Default")
      (node (ref "D4") (pin "1") (pinfunction "A_1") (pintype "passive"))
      (node (ref "JP1") (pin "1") (pinfunction "1_1") (pintype "passive"))
      (node (ref "L1") (pin "2") (pinfunction "2_2") (pintype "passive"))
    )
    (net (code "49") (name "Net-(D5-A)") (class "Default")
      (node (ref "C24") (pin "2") (pinfunction "2_2") (pintype "passive"))
      (node (ref "D5") (pin "1") (pinfunction "A_1") (pintype "passive"))
      (node (ref "Q6") (pin "4") (pinfunction "G_4") (pintype "passive"))
      (node (ref "Q7") (pin "4") (pinfunction "G_4") (pintype "passive"))
      (node (ref "R19") (pin "1") (pinfunction "1_1") (pintype "passive"))
      (node (ref "R21") (pin "2") (pinfunction "2_2") (pintype "passive"))
    )
    (net (code "50") (name "Net-(D5-K)") (class "Default")
      (node (ref "C24") (pin "1") (pinfunction "1_1") (pintype "passive"))
      (node (ref "D5") (pin "2") (pinfunction "K_2") (pintype "passive"))
      (node (ref "Q6") (pin "1") (pinfunction "S_1") (pintype "passive"))
      (node (ref "Q6") (pin "2") (pinfunction "S_2") (pintype "passive"))
      (node (ref "Q6") (pin "3") (pinfunction "S_3") (pintype "passive"))
      (node (ref "Q7") (pin "1") (pinfunction "S_1") (pintype "passive"))
      (node (ref "Q7") (pin "2") (pinfunction "S_2") (pintype "passive"))
      (node (ref "Q7") (pin "3") (pinfunction "S_3") (pintype "passive"))
      (node (ref "R19") (pin "2") (pinfunction "2_2") (pintype "passive"))
    )
    (net (code "51") (name "Net-(D6-A)") (class "Default")
      (node (ref "C22") (pin "1") (pinfunction "1_1") (pintype "passive"))
      (node (ref "D6") (pin "1") (pinfunction "A_1") (pintype "passive"))
      (node (ref "JP1") (pin "3") (pinfunction "3_3") (pintype "passive"))
      (node (ref "R17") (pin "2") (pinfunction "2_2") (pintype "passive"))
    )
    (net (code "52") (name "Net-(D7-A)") (class "Default")
      (node (ref "C23") (pin "1") (pinfunction "1_1") (pintype "passive"))
      (node (ref "D7") (pin "1") (pinfunction "A_1") (pintype "passive"))
      (node (ref "JP1") (pin "4") (pinfunction "4_4") (pintype "passive"))
      (node (ref "R18") (pin "2") (pinfunction "2_2") (pintype "passive"))
    )
    (net (code "53") (name "Net-(D8-K)") (class "Default")
      (node (ref "C25") (pin "2") (pinfunction "2_2") (pintype "passive"))
      (node (ref "D8") (pin "2") (pinfunction "K_2") (pintype "passive"))
      (node (ref "U5") (pin "14") (pinfunction "BSTC_14") (pintype "passive"))
    )
    (net (code "54") (name "Net-(D9-A)") (class "Default")
      (node (ref "C27") (pin "2") (pinfunction "2_2") (pintype "passive"))
      (node (ref "D9") (pin "1") (pinfunction "A_1") (pintype "passive"))
      (node (ref "L2") (pin "2") (pinfunction "2_2") (pintype "passive"))
    )
    (net (code "55") (name "Net-(D12-A)") (class "Default")
      (node (ref "C29") (pin "1") (pinfunction "1_1") (pintype "passive"))
      (node (ref "D12") (pin "1") (pinfunction "A_1") (pintype "passive"))
      (node (ref "D14") (pin "1") (pinfunction "A_1") (pintype "passive"))
      (node (ref "JP2") (pin "3") (pinfunction "3_3") (pintype "passive"))
    )
    (net (code "56") (name "Net-(D12-K)") (class "Default")
      (node (ref "D12") (pin "2") (pinfunction "K_2") (pintype "passive"))
      (node (ref "R22") (pin "2") (pinfunction "2_2") (pintype "passive"))
    )
    (net (code "57") (name "Net-(D13-A)") (class "Default")
      (node (ref "C28") (pin "1") (pinfunction "1_1") (pintype "passive"))
      (node (ref "D13") (pin "1") (pinfunction "A_1") (pintype "passive"))
      (node (ref "JP2") (pin "1") (pinfunction "1_1") (pintype "passive"))
      (node (ref "R20") (pin "2") (pinfunction "2_2") (pintype "passive"))
    )
    (net (code "58") (name "Net-(D16-K)") (class "Default")
      (node (ref "C34") (pin "2") (pinfunction "2_2") (pintype "passive"))
      (node (ref "D16") (pin "2") (pinfunction "K_2") (pintype "passive"))
      (node (ref "U8") (pin "4") (pinfunction "EN_4") (pintype "passive"))
      (node (ref "U8") (pin "5") (pinfunction "VIN_5") (pintype "passive"))
    )
    (net (code "59") (name "Net-(D18-A)") (class "Default")
      (node (ref "C35") (pin "1") (pinfunction "1_1") (pintype "passive"))
      (node (ref "D18") (pin "1") (pinfunction "A_1") (pintype "passive"))
      (node (ref "JP3") (pin "1") (pinfunction "1_1") (pintype "passive"))
      (node (ref "R25") (pin "2") (pinfunction "2_2") (pintype "passive"))
    )
    (net (code "60") (name "Net-(D19-A)") (class "Default")
      (node (ref "C36") (pin "1") (pinfunction "1_1") (pintype "passive"))
      (node (ref "D19") (pin "1") (pinfunction "A_1") (pintype "passive"))
      (node (ref "JP3") (pin "3") (pinfunction "3_3") (pintype "passive"))
      (node (ref "R27") (pin "2") (pinfunction "2_2") (pintype "passive"))
    )
    (net (code "61") (name "Net-(LED1-K)") (class "Default")
      (node (ref "LED1") (pin "2") (pinfunction "K_2") (pintype "passive"))
      (node (ref "R6") (pin "2") (pinfunction "2_2") (pintype "passive"))
    )
    (net (code "62") (name "Net-(LED2-K)") (class "Default")
      (node (ref "LED2") (pin "2") (pinfunction "K_2") (pintype "passive"))
      (node (ref "R7") (pin "2") (pinfunction "2_2") (pintype "passive"))
    )
    (net (code "63") (name "Net-(Q1-G)") (class "Default")
      (node (ref "Q1") (pin "4") (pinfunction "G_4") (pintype "passive"))
      (node (ref "U5") (pin "19") (pinfunction "GHA_19") (pintype "passive"))
    )
    (net (code "64") (name "Net-(Q4-G)") (class "Default")
      (node (ref "Q4") (pin "4") (pinfunction "G_4") (pintype "passive"))
      (node (ref "U5") (pin "16") (pinfunction "GHB_16") (pintype "passive"))
    )
    (net (code "65") (name "Net-(Q8-G)") (class "Default")
      (node (ref "Q8") (pin "4") (pinfunction "G_4") (pintype "passive"))
      (node (ref "U5") (pin "13") (pinfunction "GHC_13") (pintype "passive"))
    )
    (net (code "66") (name "Net-(U4-PA2)") (class "Default")
      (node (ref "C14") (pin "2") (pinfunction "2_2") (pintype "passive"))
      (node (ref "R10") (pin "1") (pinfunction "1_1") (pintype "passive"))
      (node (ref "U4") (pin "10") (pinfunction "PA2_10") (pintype "bidirectional"))
    )
    (net (code "67") (name "Net-(U4-PA4)") (class "Default")
      (node (ref "C17") (pin "1") (pinfunction "1_1") (pintype "passive"))
      (node (ref "R14") (pin "1") (pinfunction "1_1") (pintype "passive"))
      (node (ref "U4") (pin "12") (pinfunction "PA4_12") (pintype "bidirectional"))
    )
    (net (code "68") (name "Net-(U5-DT)") (class "Default")
      (node (ref "R5") (pin "1") (pinfunction "1_1") (pintype "passive"))
      (node (ref "U5") (pin "21") (pinfunction "DT_21") (pintype "passive"))
    )
    (net (code "69") (name "Net-(U8-BST)") (class "Default")
      (node (ref "C30") (pin "1") (pinfunction "1_1") (pintype "passive"))
      (node (ref "U8") (pin "1") (pinfunction "BST_1") (pintype "passive"))
    )
    (net (code "70") (name "Net-(U8-FB)") (class "Default")
      (node (ref "R28") (pin "1") (pinfunction "1_1") (pintype "passive"))
      (node (ref "R29") (pin "2") (pinfunction "2_2") (pintype "passive"))
      (node (ref "U8") (pin "3") (pinfunction "FB_3") (pintype "passive"))
    )
    (net (code "71") (name "Net-(U8-SW)") (class "Default")
      (node (ref "C30") (pin "2") (pinfunction "2_2") (pintype "passive"))
      (node (ref "L3") (pin "1") (pinfunction "1_1") (pintype "passive"))
      (node (ref "U8") (pin "6") (pinfunction "SW_6") (pintype "passive"))
    )
    (net (code "72") (name "VBAT") (class "Default")
      (node (ref "C1") (pin "1") (pinfunction "1_1") (pintype "passive"))
      (node (ref "C2") (pin "1") (pinfunction "1_1") (pintype "passive"))
      (node (ref "C3") (pin "1") (pinfunction "1_1") (pintype "passive"))
      (node (ref "C4") (pin "1") (pinfunction "1_1") (pintype "passive"))
      (node (ref "C5") (pin "1") (pinfunction "1_1") (pintype "passive"))
      (node (ref "C6") (pin "1") (pinfunction "1_1") (pintype "passive"))
      (node (ref "D16") (pin "1") (pinfunction "A_1") (pintype "passive"))
      (node (ref "Q1") (pin "5") (pinfunction "D_5") (pintype "passive"))
      (node (ref "Q1") (pin "6") (pinfunction "D_6") (pintype "passive"))
      (node (ref "Q1") (pin "7") (pinfunction "D_7") (pintype "passive"))
      (node (ref "Q1") (pin "8") (pinfunction "D_8") (pintype "passive"))
      (node (ref "Q1") (pin "9") (pinfunction "D_9") (pintype "passive"))
      (node (ref "Q4") (pin "5") (pinfunction "D_5") (pintype "passive"))
      (node (ref "Q4") (pin "6") (pinfunction "D_6") (pintype "passive"))
      (node (ref "Q4") (pin "7") (pinfunction "D_7") (pintype "passive"))
      (node (ref "Q4") (pin "8") (pinfunction "D_8") (pintype "passive"))
      (node (ref "Q4") (pin "9") (pinfunction "D_9") (pintype "passive"))
      (node (ref "Q7") (pin "5") (pinfunction "D_5") (pintype "passive"))
      (node (ref "Q7") (pin "6") (pinfunction "D_6") (pintype "passive"))
      (node (ref "Q7") (pin "7") (pinfunction "D_7") (pintype "passive"))
      (node (ref "Q7") (pin "8") (pinfunction "D_8") (pintype "passive"))
      (node (ref "Q7") (pin "9") (pinfunction "D_9") (pintype "passive"))
      (node (ref "Q8") (pin "5") (pinfunction "D_5") (pintype "passive"))
      (node (ref "Q8") (pin "6") (pinfunction "D_6") (pintype "passive"))
      (node (ref "Q8") (pin "7") (pinfunction "D_7") (pintype "passive"))
      (node (ref "Q8") (pin "8") (pinfunction "D_8") (pintype "passive"))
      (node (ref "Q8") (pin "9") (pinfunction "D_9") (pintype "passive"))
      (node (ref "R11") (pin "1") (pinfunction "1_1") (pintype "passive"))
      (node (ref "R13") (pin "2") (pinfunction "2_2") (pintype "passive"))
    )
    (net (code "73") (name "VBAT_IN") (class "Default")
      (node (ref "C26") (pin "1") (pinfunction "1_1") (pintype "passive"))
      (node (ref "D10") (pin "2") (pinfunction "K_2") (pintype "passive"))
      (node (ref "P1") (pin "1") (pinfunction "P_1") (pintype "passive"))
      (node (ref "Q6") (pin "5") (pinfunction "D_5") (pintype "passive"))
      (node (ref "Q6") (pin "6") (pinfunction "D_6") (pintype "passive"))
      (node (ref "Q6") (pin "7") (pinfunction "D_7") (pintype "passive"))
      (node (ref "Q6") (pin "8") (pinfunction "D_8") (pintype "passive"))
      (node (ref "Q6") (pin "9") (pinfunction "D_9") (pintype "passive"))
    )
    (net (code "74") (name "unconnected-(U1-NC-Pad1)") (class "Default")
      (node (ref "U1") (pin "1") (pinfunction "NC_1") (pintype "passive+no_connect"))
    )
    (net (code "75") (name "unconnected-(U2-NC-Pad1)") (class "Default")
      (node (ref "U2") (pin "1") (pinfunction "NC_1") (pintype "passive+no_connect"))
    )
    (net (code "76") (name "unconnected-(U4-PA0-Pad8)") (class "Default")
      (node (ref "U4") (pin "8") (pinfunction "PA0_8") (pintype "bidirectional"))
    )
    (net (code "77") (name "unconnected-(U4-PA1-Pad9)") (class "Default")
      (node (ref "U4") (pin "9") (pinfunction "PA1_9") (pintype "bidirectional"))
    )
    (net (code "78") (name "unconnected-(U4-PA3-Pad11)") (class "Default")
      (node (ref "U4") (pin "11") (pinfunction "PA3_11") (pintype "bidirectional"))
    )
    (net (code "79") (name "unconnected-(U4-PA15-Pad38)") (class "Default")
      (node (ref "U4") (pin "38") (pinfunction "PA15_38") (pintype "bidirectional"))
    )
    (net (code "80") (name "unconnected-(U4-PB0-Pad17)") (class "Default")
      (node (ref "U4") (pin "17") (pinfunction "PB0_17") (pintype "bidirectional"))
    )
    (net (code "81") (name "unconnected-(U4-PB3-Pad41)") (class "Default")
      (node (ref "U4") (pin "41") (pinfunction "PB3_41") (pintype "bidirectional"))
    )
    (net (code "82") (name "unconnected-(U4-PB10-Pad22)") (class "Default")
      (node (ref "U4") (pin "22") (pinfunction "PB10_22") (pintype "bidirectional"))
    )
    (net (code "83") (name "unconnected-(U4-PB12-Pad25)") (class "Default")
      (node (ref "U4") (pin "25") (pinfunction "PB12_25") (pintype "bidirectional"))
    )
    (net (code "84") (name "unconnected-(U4-PC6-Pad29)") (class "Default")
      (node (ref "U4") (pin "29") (pinfunction "PC6_29") (pintype "bidirectional"))
    )
    (net (code "85") (name "unconnected-(U4-PC13-Pad2)") (class "Default")
      (node (ref "U4") (pin "2") (pinfunction "PC13_2") (pintype "bidirectional"))
    )
    (net (code "86") (name "unconnected-(U4-PC14-OSC32_IN-Pad3)") (class "Default")
      (node (ref "U4") (pin "3") (pinfunction "PC14-OSC32_IN_3") (pintype "bidirectional"))
    )
    (net (code "87") (name "unconnected-(U4-PC15-OSC32_OUT-Pad4)") (class "Default")
      (node (ref "U4") (pin "4") (pinfunction "PC15-OSC32_OUT_4") (pintype "bidirectional"))
    )
    (net (code "88") (name "unconnected-(U4-PF0-OSC_IN-Pad5)") (class "Default")
      (node (ref "U4") (pin "5") (pinfunction "PF0-OSC_IN_5") (pintype "bidirectional"))
    )
    (net (code "89") (name "unconnected-(U4-PF1-OSC_OUT-Pad6)") (class "Default")
      (node (ref "U4") (pin "6") (pinfunction "PF1-OSC_OUT_6") (pintype "bidirectional"))
    )
    (net (code "90") (name "unconnected-(U5-MODE-Pad5)") (class "Default")
      (node (ref "U5") (pin "5") (pinfunction "MODE_5") (pintype "passive+no_connect"))
    )
    (net (code "91") (name "unconnected-(U5-NC-Pad7)") (class "Default")
      (node (ref "U5") (pin "7") (pinfunction "NC_7") (pintype "passive+no_connect"))
    )
    (net (code "92") (name "unconnected-(U5-NC-Pad8)") (class "Default")
      (node (ref "U5") (pin "8") (pinfunction "NC_8") (pintype "passive+no_connect"))
    )
    (net (code "93") (name "unconnected-(U6-A-Pad16)") (class "Default")
      (node (ref "U6") (pin "16") (pinfunction "A_16") (pintype "passive+no_connect"))
    )
    (net (code "94") (name "unconnected-(U6-B-Pad15)") (class "Default")
      (node (ref "U6") (pin "15") (pinfunction "B_15") (pintype "passive+no_connect"))
    )
    (net (code "95") (name "unconnected-(U6-CAL_EN-Pad4)") (class "Default")
      (node (ref "U6") (pin "4") (pinfunction "CAL_EN_4") (pintype "passive+no_connect"))
    )
    (net (code "96") (name "unconnected-(U6-OUT-Pad10)") (class "Default")
      (node (ref "U6") (pin "10") (pinfunction "OUT_10") (pintype "passive+no_connect"))
    )
    (net (code "97") (name "unconnected-(U6-TEST-Pad11)") (class "Default")
      (node (ref "U6") (pin "11") (pinfunction "TEST_11") (pintype "passive+no_connect"))
    )
    (net (code "98") (name "unconnected-(U6-TEST_EN-Pad13)") (class "Default")
      (node (ref "U6") (pin "13") (pinfunction "TEST_EN_13") (pintype "passive+no_connect"))
    )
    (net (code "99") (name "unconnected-(U6-U-Pad1)") (class "Default")
      (node (ref "U6") (pin "1") (pinfunction "U_1") (pintype "passive+no_connect"))
    )
    (net (code "100") (name "unconnected-(U6-V-Pad2)") (class "Default")
      (node (ref "U6") (pin "2") (pinfunction "V_2") (pintype "passive+no_connect"))
    )
    (net (code "101") (name "unconnected-(U6-W-Pad3)") (class "Default")
      (node (ref "U6") (pin "3") (pinfunction "W_3") (pintype "passive+no_connect"))
    )
    (net (code "102") (name "unconnected-(U6-Z-Pad14)") (class "Default")
      (node (ref "U6") (pin "14") (pinfunction "Z_14") (pintype "passive+no_connect"))
    )
    (net (code "103") (name "unconnected-(U7-NC-Pad4)") (class "Default")
      (node (ref "U7") (pin "4") (pinfunction "NC_4") (pintype "passive+no_connect"))
    )
    (net (code "104") (name "unconnected-(USB1-Pad0)") (class "Default")
      (node (ref "USB1") (pin "0") (pinfunction "0_0") (pintype "passive+no_connect"))
    )
    (net (code "105") (name "unconnected-(USB1-Pad0)_1") (class "Default")
      (node (ref "USB1") (pin "0") (pinfunction "0_0") (pintype "passive+no_connect"))
    )
    (net (code "106") (name "unconnected-(USB1-Pad0)_2") (class "Default")
      (node (ref "USB1") (pin "0") (pinfunction "0_0") (pintype "passive+no_connect"))
    )
    (net (code "107") (name "unconnected-(USB1-Pad0)_3") (class "Default")
      (node (ref "USB1") (pin "0") (pinfunction "0_0") (pintype "passive+no_connect"))
    )
    (net (code "108") (name "unconnected-(USB1-SBU1-PadA8)") (class "Default")
      (node (ref "USB1") (pin "A8") (pinfunction "SBU1_A8") (pintype "passive+no_connect"))
    )
    (net (code "109") (name "unconnected-(USB1-SBU2-PadB8)") (class "Default")
      (node (ref "USB1") (pin "B8") (pinfunction "SBU2_B8") (pintype "passive+no_connect"))
    )
  )
)
